# Plasma_speaker.net
KiCad netlist of a schematic drawn in EAGLE
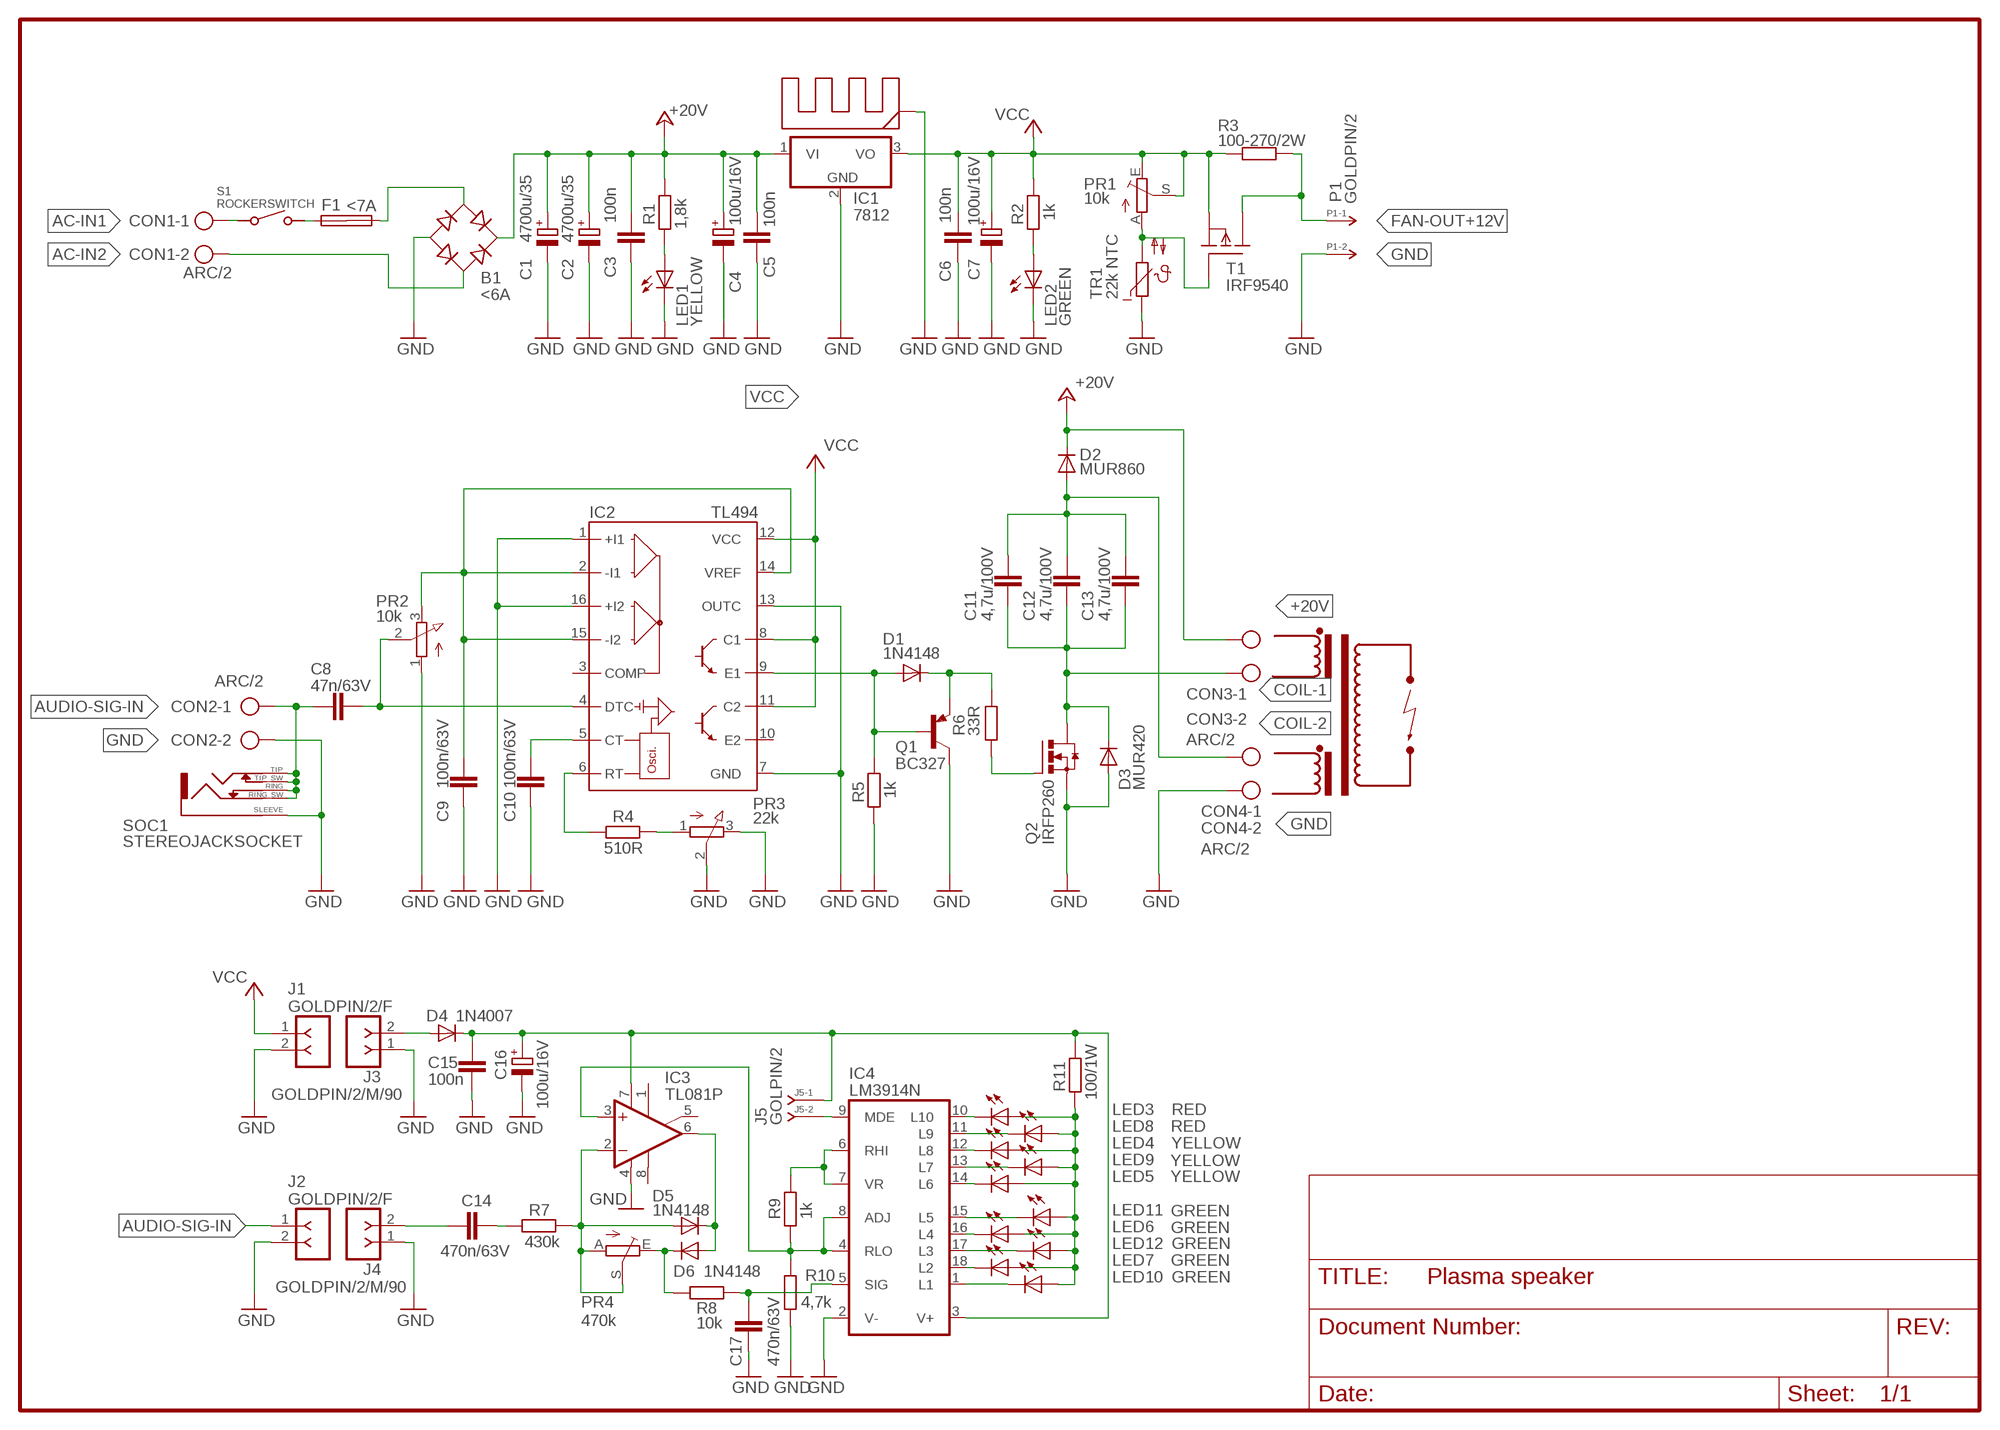
[diagram p0: schematic, sheet 1]

(export (version "E")
  (design (tool "Eeschema 10.0.6"))
  (components
    (comp (ref "B1")
      (value "<6A")
      (footprint "eagle-import:SKB32")
      (libsource (lib "eagle-import") (part "RECTIFIER-SKB32"))
    )
    (comp (ref "C1")
      (value "4700u/35")
      (footprint "eagle-import:E7,5-18")
      (libsource (lib "eagle-import") (part "CPOL-EUE7.5-18"))
    )
    (comp (ref "C2")
      (value "4700u/35")
      (footprint "eagle-import:E7,5-18")
      (libsource (lib "eagle-import") (part "CPOL-EUE7.5-18"))
    )
    (comp (ref "C3")
      (value "100n")
      (footprint "eagle-import:C025-025X050")
      (libsource (lib "eagle-import") (part "C-EU025-025X050"))
    )
    (comp (ref "C4")
      (value "100u/16V")
      (footprint "eagle-import:E2,5-5")
      (libsource (lib "eagle-import") (part "CPOL-EUE2.5-5"))
    )
    (comp (ref "C5")
      (value "100n")
      (footprint "eagle-import:C025-025X050")
      (libsource (lib "eagle-import") (part "C-EU025-025X050"))
    )
    (comp (ref "C6")
      (value "100n")
      (footprint "eagle-import:C025-025X050")
      (libsource (lib "eagle-import") (part "C-EU025-025X050"))
    )
    (comp (ref "C7")
      (value "100u/16V")
      (footprint "eagle-import:E2,5-5")
      (libsource (lib "eagle-import") (part "CPOL-EUE2.5-5"))
    )
    (comp (ref "C8")
      (value "47n/63V")
      (footprint "eagle-import:C050-025X075")
      (libsource (lib "eagle-import") (part "C-EU050-025X075"))
    )
    (comp (ref "C9")
      (value "100n/63V")
      (footprint "eagle-import:C050-025X075")
      (libsource (lib "eagle-import") (part "C-EU050-025X075"))
    )
    (comp (ref "C10")
      (value "100n/63V")
      (footprint "eagle-import:C050-025X075")
      (libsource (lib "eagle-import") (part "C-EU050-025X075"))
    )
    (comp (ref "C11")
      (value "4,7u/100V")
      (footprint "eagle-import:C275-093X316")
      (libsource (lib "eagle-import") (part "C-EU275-093X316"))
    )
    (comp (ref "C12")
      (value "4,7u/100V")
      (footprint "eagle-import:C275-093X316")
      (libsource (lib "eagle-import") (part "C-EU275-093X316"))
    )
    (comp (ref "C13")
      (value "4,7u/100V")
      (footprint "eagle-import:C275-093X316")
      (libsource (lib "eagle-import") (part "C-EU275-093X316"))
    )
    (comp (ref "C14")
      (value "470n/63V")
      (footprint "eagle-import:C050-050X075")
      (libsource (lib "eagle-import") (part "C-EU050-050X075"))
    )
    (comp (ref "C15")
      (value "100n")
      (footprint "eagle-import:C025-025X050")
      (libsource (lib "eagle-import") (part "C-EU025-025X050"))
    )
    (comp (ref "C16")
      (value "100u/16V")
      (footprint "eagle-import:E2,5-5")
      (libsource (lib "eagle-import") (part "CPOL-EUE2.5-5"))
    )
    (comp (ref "C17")
      (value "470n/63V")
      (footprint "eagle-import:C050-050X075")
      (libsource (lib "eagle-import") (part "C-EU050-050X075"))
    )
    (comp (ref "CON1")
      (value "ARC/2")
      (footprint "eagle-import:AK300_2")
      (libsource (lib "eagle-import") (part "AK300/2"))
    )
    (comp (ref "CON2")
      (value "ARC/2")
      (footprint "eagle-import:AK300_2")
      (libsource (lib "eagle-import") (part "AK300/2"))
    )
    (comp (ref "CON3")
      (value "ARC/2")
      (footprint "eagle-import:AK300_2")
      (libsource (lib "eagle-import") (part "AK300/2"))
    )
    (comp (ref "CON4")
      (value "ARC/2")
      (footprint "eagle-import:AK300_2")
      (libsource (lib "eagle-import") (part "AK300/2"))
    )
    (comp (ref "D1")
      (value "1N4148")
      (footprint "eagle-import:DO35-7")
      (libsource (lib "eagle-import") (part "1N4148DO35-7"))
    )
    (comp (ref "D2")
      (value "MUR860")
      (footprint "eagle-import:TO220ACS")
      (libsource (lib "eagle-import") (part "BYT08P"))
    )
    (comp (ref "D3")
      (value "MUR420")
      (footprint "eagle-import:SGA-10")
      (libsource (lib "eagle-import") (part "BY203"))
    )
    (comp (ref "D4")
      (value "1N4007")
      (footprint "eagle-import:DO41-10")
      (libsource (lib "eagle-import") (part "1N4004"))
    )
    (comp (ref "D5")
      (value "1N4148")
      (footprint "eagle-import:DO35-7")
      (libsource (lib "eagle-import") (part "1N4148DO35-7"))
    )
    (comp (ref "D6")
      (value "1N4148")
      (footprint "eagle-import:DO35-7")
      (libsource (lib "eagle-import") (part "1N4148DO35-7"))
    )
    (comp (ref "F1")
      (value "<7A")
      (footprint "eagle-import:SHK20L")
      (libsource (lib "eagle-import") (part "SHK20L"))
    )
    (comp (ref "IC1")
      (value "7812")
      (footprint "eagle-import:TO220V")
      (libsource (lib "eagle-import") (part "78TV12"))
    )
    (comp (ref "IC2")
      (value "TL494")
      (footprint "eagle-import:DIL16")
      (libsource (lib "eagle-import") (part "TL494NC"))
    )
    (comp (ref "IC3")
      (value "TL081P")
      (footprint "eagle-import:DIL08")
      (libsource (lib "eagle-import") (part "TL081P"))
    )
    (comp (ref "IC4")
      (value "LM3914N")
      (footprint "eagle-import:DIL18")
      (libsource (lib "eagle-import") (part "LM3914N"))
    )
    (comp (ref "J1")
      (value "GOLDPIN/2/F")
      (footprint "eagle-import:SIP-100-02-40Y")
      (libsource (lib "eagle-import") (part "F-1X02-SIP-100-40Y"))
    )
    (comp (ref "J2")
      (value "GOLDPIN/2/F")
      (footprint "eagle-import:SIP-100-02-40Y")
      (libsource (lib "eagle-import") (part "F-1X02-SIP-100-40Y"))
    )
    (comp (ref "J3")
      (value "GOLDPIN/2/M/90")
      (footprint "eagle-import:KK-4455-A02")
      (libsource (lib "eagle-import") (part "F-1X02-KK-4455-A02"))
    )
    (comp (ref "J4")
      (value "GOLDPIN/2/M/90")
      (footprint "eagle-import:KK-4455-A02")
      (libsource (lib "eagle-import") (part "F-1X02-KK-4455-A02"))
    )
    (comp (ref "J5")
      (value "GOLPIN/2")
      (footprint "eagle-import:SIP-100-02-40Y")
      (libsource (lib "eagle-import") (part "J-02-SIP-100-40Y"))
    )
    (comp (ref "LED1")
      (value "YELLOW")
      (footprint "eagle-import:LED5MM")
      (libsource (lib "eagle-import") (part "LED5MM"))
    )
    (comp (ref "LED2")
      (value "GREEN")
      (footprint "eagle-import:LED5MM")
      (libsource (lib "eagle-import") (part "LED5MM"))
    )
    (comp (ref "LED3")
      (value "RED")
      (footprint "eagle-import:LED5MM")
      (libsource (lib "eagle-import") (part "LED5MM"))
    )
    (comp (ref "LED4")
      (value "YELLOW")
      (footprint "eagle-import:LED5MM")
      (libsource (lib "eagle-import") (part "LED5MM"))
    )
    (comp (ref "LED5")
      (value "YELLOW")
      (footprint "eagle-import:LED5MM")
      (libsource (lib "eagle-import") (part "LED5MM"))
    )
    (comp (ref "LED6")
      (value "GREEN")
      (footprint "eagle-import:LED5MM")
      (libsource (lib "eagle-import") (part "LED5MM"))
    )
    (comp (ref "LED7")
      (value "GREEN")
      (footprint "eagle-import:LED5MM")
      (libsource (lib "eagle-import") (part "LED5MM"))
    )
    (comp (ref "LED8")
      (value "RED")
      (footprint "eagle-import:LED5MM")
      (libsource (lib "eagle-import") (part "LED5MM"))
    )
    (comp (ref "LED9")
      (value "YELLOW")
      (footprint "eagle-import:LED5MM")
      (libsource (lib "eagle-import") (part "LED5MM"))
    )
    (comp (ref "LED10")
      (value "GREEN")
      (footprint "eagle-import:LED5MM")
      (libsource (lib "eagle-import") (part "LED5MM"))
    )
    (comp (ref "LED11")
      (value "GREEN")
      (footprint "eagle-import:LED5MM")
      (libsource (lib "eagle-import") (part "LED5MM"))
    )
    (comp (ref "LED12")
      (value "GREEN")
      (footprint "eagle-import:LED5MM")
      (libsource (lib "eagle-import") (part "LED5MM"))
    )
    (comp (ref "P1")
      (value "GOLDPIN/2")
      (footprint "eagle-import:SIP-100-02-40Y")
      (libsource (lib "eagle-import") (part "P-02-SIP-100-40Y"))
    )
    (comp (ref "PR1")
      (value "10k")
      (footprint "eagle-import:CA6V")
      (libsource (lib "eagle-import") (part "TRIM_EU-CA6V"))
    )
    (comp (ref "PR2")
      (value "10k")
      (footprint "eagle-import:3RP_1610N")
      (libsource (lib "eagle-import") (part "3RP/1610N"))
    )
    (comp (ref "PR3")
      (value "22k")
      (footprint "eagle-import:3RP_1610N")
      (libsource (lib "eagle-import") (part "3RP/1610N"))
    )
    (comp (ref "PR4")
      (value "470k")
      (footprint "eagle-import:CA6V")
      (libsource (lib "eagle-import") (part "TRIM_EU-CA6V"))
    )
    (comp (ref "Q1")
      (value "BC327")
      (footprint "eagle-import:TO92-EBC")
      (libsource (lib "eagle-import") (part "-PNP-TO92-EBCBC327-25"))
    )
    (comp (ref "Q2")
      (value "IRFP260")
      (footprint "eagle-import:TO247BV")
      (libsource (lib "eagle-import") (part "IRFP240"))
    )
    (comp (ref "R1")
      (value "1,8k")
      (footprint "eagle-import:0204_7")
      (libsource (lib "eagle-import") (part "R-EU_0204/7"))
    )
    (comp (ref "R2")
      (value "1k")
      (footprint "eagle-import:0204_7")
      (libsource (lib "eagle-import") (part "R-EU_0204/7"))
    )
    (comp (ref "R3")
      (value "100-270/2W")
      (footprint "eagle-import:0309_12")
      (libsource (lib "eagle-import") (part "R-EU_0309/12"))
    )
    (comp (ref "R4")
      (value "510R")
      (footprint "eagle-import:0204_7")
      (libsource (lib "eagle-import") (part "R-EU_0204/7"))
    )
    (comp (ref "R5")
      (value "1k")
      (footprint "eagle-import:0204_7")
      (libsource (lib "eagle-import") (part "R-EU_0204/7"))
    )
    (comp (ref "R6")
      (value "33R")
      (footprint "eagle-import:0207_10")
      (libsource (lib "eagle-import") (part "R-EU_0207/10"))
    )
    (comp (ref "R7")
      (value "430k")
      (footprint "eagle-import:0204_7")
      (libsource (lib "eagle-import") (part "R-EU_0204/7"))
    )
    (comp (ref "R8")
      (value "10k")
      (footprint "eagle-import:0204_7")
      (libsource (lib "eagle-import") (part "R-EU_0204/7"))
    )
    (comp (ref "R9")
      (value "1k")
      (footprint "eagle-import:0204_7")
      (libsource (lib "eagle-import") (part "R-EU_0204/7"))
    )
    (comp (ref "R10")
      (value "4,7k")
      (footprint "eagle-import:0204_7")
      (libsource (lib "eagle-import") (part "R-EU_0204/7"))
    )
    (comp (ref "R11")
      (value "100/1W")
      (footprint "eagle-import:0411_15")
      (libsource (lib "eagle-import") (part "R-EU_0411/15"))
    )
    (comp (ref "RAD1")
      (value "TO3")
      (footprint "eagle-import:RADIATOR")
      (libsource (lib "eagle-import") (part "RADIATOR-A"))
    )
    (comp (ref "S1")
      (value "ROCKERSWITCH")
      (footprint "eagle-import:ROCKER")
      (libsource (lib "eagle-import") (part "ROCKERSWITCH"))
    )
    (comp (ref "SOC1")
      (value "STEREOJACKSOCKET")
      (footprint "eagle-import:PICAXE_STEREOJACKSOCKET")
      (libsource (lib "eagle-import") (part "PICAXE_STEREOJACKSOCKET"))
    )
    (comp (ref "T1")
      (value "IRF9540")
      (footprint "eagle-import:TO220")
      (libsource (lib "eagle-import") (part "IRF9530"))
    )
    (comp (ref "TR1")
      (value "22k NTC")
      (footprint "eagle-import:P640")
      (libsource (lib "eagle-import") (part "NTC640"))
    )
  )
  (nets
    (net (code "1") (name "+20V") (class "Default")
      (node (ref "B1") (pin "+") (pinfunction "+_+") (pintype "passive"))
      (node (ref "C1") (pin "+") (pinfunction "+_+") (pintype "passive"))
      (node (ref "C2") (pin "+") (pinfunction "+_+") (pintype "passive"))
      (node (ref "C3") (pin "1") (pinfunction "1_1") (pintype "passive"))
      (node (ref "C4") (pin "+") (pinfunction "+_+") (pintype "passive"))
      (node (ref "C5") (pin "1") (pinfunction "1_1") (pintype "passive"))
      (node (ref "CON3") (pin "1") (pinfunction "KL_1") (pintype "passive"))
      (node (ref "D2") (pin "C") (pinfunction "C_C") (pintype "passive"))
      (node (ref "IC1") (pin "1") (pinfunction "VI_1") (pintype "input"))
      (node (ref "R1") (pin "1") (pinfunction "1_1") (pintype "passive"))
    )
    (net (code "2") (name "AC-IN1") (class "Default")
      (node (ref "CON1") (pin "1") (pinfunction "KL_1") (pintype "passive"))
      (node (ref "S1") (pin "IN1") (pinfunction "IN_IN1") (pintype "input"))
      (node (ref "S1") (pin "IN2") (pinfunction "IN_IN2") (pintype "input"))
    )
    (net (code "3") (name "AC-IN2") (class "Default")
      (node (ref "B1") (pin "AC2") (pinfunction "AC2_AC2") (pintype "passive"))
      (node (ref "CON1") (pin "2") (pinfunction "KL_2") (pintype "passive"))
    )
    (net (code "4") (name "AUDIO-SIG-IN") (class "Default")
      (node (ref "C8") (pin "2") (pinfunction "2_2") (pintype "passive"))
      (node (ref "CON2") (pin "1") (pinfunction "KL_1") (pintype "passive"))
      (node (ref "J2") (pin "1") (pinfunction "1_1") (pintype "passive"))
      (node (ref "SOC1") (pin "RING") (pinfunction "RING_RING") (pintype "bidirectional"))
      (node (ref "SOC1") (pin "RING_SW") (pinfunction "RING-SW_RING_SW") (pintype "bidirectional"))
      (node (ref "SOC1") (pin "TIP") (pinfunction "TIP_TIP") (pintype "bidirectional"))
      (node (ref "SOC1") (pin "TIP_SW") (pinfunction "TIP-SW_TIP_SW") (pintype "bidirectional"))
    )
    (net (code "5") (name "COIL-1") (class "Default")
      (node (ref "C11") (pin "2") (pinfunction "2_2") (pintype "passive"))
      (node (ref "C12") (pin "2") (pinfunction "2_2") (pintype "passive"))
      (node (ref "C13") (pin "2") (pinfunction "2_2") (pintype "passive"))
      (node (ref "CON3") (pin "2") (pinfunction "KL_2") (pintype "passive"))
      (node (ref "D3") (pin "C") (pinfunction "C_C") (pintype "passive"))
      (node (ref "Q2") (pin "D") (pinfunction "D_D") (pintype "passive"))
    )
    (net (code "6") (name "COIL-2") (class "Default")
      (node (ref "C11") (pin "1") (pinfunction "1_1") (pintype "passive"))
      (node (ref "C12") (pin "1") (pinfunction "1_1") (pintype "passive"))
      (node (ref "C13") (pin "1") (pinfunction "1_1") (pintype "passive"))
      (node (ref "CON4") (pin "1") (pinfunction "KL_1") (pintype "passive"))
      (node (ref "D2") (pin "A") (pinfunction "A_A") (pintype "passive"))
    )
    (net (code "7") (name "FAN-OUT+12V") (class "Default")
      (node (ref "P1") (pin "1") (pinfunction "P_1") (pintype "passive"))
      (node (ref "R3") (pin "2") (pinfunction "2_2") (pintype "passive"))
      (node (ref "T1") (pin "2") (pinfunction "D_2") (pintype "passive"))
    )
    (net (code "8") (name "GND") (class "Default")
      (node (ref "B1") (pin "-") (pinfunction "-_-") (pintype "passive"))
      (node (ref "C1") (pin "-") (pinfunction "-_-") (pintype "passive"))
      (node (ref "C10") (pin "2") (pinfunction "2_2") (pintype "passive"))
      (node (ref "C15") (pin "2") (pinfunction "2_2") (pintype "passive"))
      (node (ref "C16") (pin "-") (pinfunction "-_-") (pintype "passive"))
      (node (ref "C17") (pin "1") (pinfunction "1_1") (pintype "passive"))
      (node (ref "C2") (pin "-") (pinfunction "-_-") (pintype "passive"))
      (node (ref "C3") (pin "2") (pinfunction "2_2") (pintype "passive"))
      (node (ref "C4") (pin "-") (pinfunction "-_-") (pintype "passive"))
      (node (ref "C5") (pin "2") (pinfunction "2_2") (pintype "passive"))
      (node (ref "C6") (pin "2") (pinfunction "2_2") (pintype "passive"))
      (node (ref "C7") (pin "-") (pinfunction "-_-") (pintype "passive"))
      (node (ref "C9") (pin "2") (pinfunction "2_2") (pintype "passive"))
      (node (ref "CON2") (pin "2") (pinfunction "KL_2") (pintype "passive"))
      (node (ref "CON4") (pin "2") (pinfunction "KL_2") (pintype "passive"))
      (node (ref "D3") (pin "A") (pinfunction "A_A") (pintype "passive"))
      (node (ref "IC1") (pin "2") (pinfunction "GND_2") (pintype "passive"))
      (node (ref "IC2") (pin "1") (pinfunction "+I1_1") (pintype "input"))
      (node (ref "IC2") (pin "13") (pinfunction "OUTC_13") (pintype "output"))
      (node (ref "IC2") (pin "16") (pinfunction "+I2_16") (pintype "input"))
      (node (ref "IC2") (pin "7") (pinfunction "GND_7") (pintype "power_in"))
      (node (ref "IC3") (pin "4") (pinfunction "V-_4") (pintype "power_in"))
      (node (ref "IC4") (pin "2") (pinfunction "V-_2") (pintype "power_in"))
      (node (ref "J1") (pin "2") (pinfunction "2_2") (pintype "passive"))
      (node (ref "J2") (pin "2") (pinfunction "2_2") (pintype "passive"))
      (node (ref "J3") (pin "1") (pinfunction "1_1") (pintype "passive"))
      (node (ref "J4") (pin "1") (pinfunction "1_1") (pintype "passive"))
      (node (ref "LED1") (pin "K") (pinfunction "C_K") (pintype "passive"))
      (node (ref "LED2") (pin "K") (pinfunction "C_K") (pintype "passive"))
      (node (ref "P1") (pin "2") (pinfunction "P_2") (pintype "passive"))
      (node (ref "PR2") (pin "1") (pinfunction "A_1") (pintype "passive"))
      (node (ref "PR3") (pin "2") (pinfunction "S_2") (pintype "passive"))
      (node (ref "PR3") (pin "3") (pinfunction "E_3") (pintype "passive"))
      (node (ref "Q1") (pin "C") (pinfunction "C_C") (pintype "passive"))
      (node (ref "Q2") (pin "S") (pinfunction "S_S") (pintype "passive"))
      (node (ref "R10") (pin "2") (pinfunction "2_2") (pintype "passive"))
      (node (ref "R5") (pin "1") (pinfunction "1_1") (pintype "passive"))
      (node (ref "RAD1") (pin "GND") (pinfunction "P$1_GND") (pintype "bidirectional"))
      (node (ref "SOC1") (pin "SLEEVE") (pinfunction "SLEEVE_SLEEVE") (pintype "bidirectional"))
      (node (ref "TR1") (pin "1") (pinfunction "1_1") (pintype "passive"))
    )
    (net (code "9") (name "Net-(B1-PadAC1)") (class "Default")
      (node (ref "B1") (pin "AC1") (pinfunction "AC1_AC1") (pintype "passive"))
      (node (ref "F1") (pin "2A") (pinfunction "2A_2A") (pintype "passive"))
    )
    (net (code "10") (name "Net-(C14-Pad1)") (class "Default")
      (node (ref "C14") (pin "1") (pinfunction "1_1") (pintype "passive"))
      (node (ref "J4") (pin "2") (pinfunction "2_2") (pintype "passive"))
    )
    (net (code "11") (name "Net-(C14-Pad2)") (class "Default")
      (node (ref "C14") (pin "2") (pinfunction "2_2") (pintype "passive"))
      (node (ref "R7") (pin "2") (pinfunction "2_2") (pintype "passive"))
    )
    (net (code "12") (name "Net-(D1-PadC)") (class "Default")
      (node (ref "D1") (pin "C") (pinfunction "C_C") (pintype "passive"))
      (node (ref "Q1") (pin "E") (pinfunction "E_E") (pintype "passive"))
      (node (ref "R6") (pin "2") (pinfunction "2_2") (pintype "passive"))
    )
    (net (code "13") (name "Net-(D4-PadA)") (class "Default")
      (node (ref "D4") (pin "A") (pinfunction "A_A") (pintype "passive"))
      (node (ref "J3") (pin "2") (pinfunction "2_2") (pintype "passive"))
    )
    (net (code "14") (name "Net-(D6-PadC)") (class "Default")
      (node (ref "D6") (pin "C") (pinfunction "C_C") (pintype "passive"))
      (node (ref "PR4") (pin "E") (pinfunction "E_E") (pintype "passive"))
      (node (ref "R8") (pin "2") (pinfunction "2_2") (pintype "passive"))
    )
    (net (code "15") (name "Net-(F1-Pad1A)") (class "Default")
      (node (ref "F1") (pin "1A") (pinfunction "1A_1A") (pintype "passive"))
      (node (ref "S1") (pin "OUT") (pinfunction "OUT_OUT") (pintype "output"))
    )
    (net (code "16") (name "Net-(IC2--I1)") (class "Default")
      (node (ref "C9") (pin "1") (pinfunction "1_1") (pintype "passive"))
      (node (ref "IC2") (pin "14") (pinfunction "VREF_14") (pintype "input"))
      (node (ref "IC2") (pin "15") (pinfunction "-I2_15") (pintype "input"))
      (node (ref "IC2") (pin "2") (pinfunction "-I1_2") (pintype "input"))
      (node (ref "PR2") (pin "3") (pinfunction "E_3") (pintype "passive"))
    )
    (net (code "17") (name "Net-(IC2-CT)") (class "Default")
      (node (ref "C10") (pin "1") (pinfunction "1_1") (pintype "passive"))
      (node (ref "IC2") (pin "5") (pinfunction "CT_5") (pintype "input"))
    )
    (net (code "18") (name "Net-(IC2-DTC)") (class "Default")
      (node (ref "C8") (pin "1") (pinfunction "1_1") (pintype "passive"))
      (node (ref "IC2") (pin "4") (pinfunction "DTC_4") (pintype "input"))
      (node (ref "PR2") (pin "2") (pinfunction "S_2") (pintype "passive"))
    )
    (net (code "19") (name "Net-(IC2-E1)") (class "Default")
      (node (ref "D1") (pin "A") (pinfunction "A_A") (pintype "passive"))
      (node (ref "IC2") (pin "9") (pinfunction "E1_9") (pintype "passive"))
      (node (ref "Q1") (pin "B") (pinfunction "B_B") (pintype "passive"))
      (node (ref "R5") (pin "2") (pinfunction "2_2") (pintype "passive"))
    )
    (net (code "20") (name "Net-(IC2-RT)") (class "Default")
      (node (ref "IC2") (pin "6") (pinfunction "RT_6") (pintype "input"))
      (node (ref "R4") (pin "2") (pinfunction "2_2") (pintype "passive"))
    )
    (net (code "21") (name "Net-(IC3-+IN)") (class "Default")
      (node (ref "IC3") (pin "3") (pinfunction "+IN_3") (pintype "input"))
      (node (ref "IC4") (pin "4") (pinfunction "RLO_4") (pintype "input"))
      (node (ref "IC4") (pin "8") (pinfunction "ADJ_8") (pintype "input"))
      (node (ref "R10") (pin "1") (pinfunction "1_1") (pintype "passive"))
      (node (ref "R9") (pin "2") (pinfunction "2_2") (pintype "passive"))
    )
    (net (code "22") (name "Net-(IC3--IN)") (class "Default")
      (node (ref "D5") (pin "A") (pinfunction "A_A") (pintype "passive"))
      (node (ref "IC3") (pin "2") (pinfunction "-IN_2") (pintype "input"))
      (node (ref "PR4") (pin "A") (pinfunction "A_A") (pintype "passive"))
      (node (ref "PR4") (pin "S") (pinfunction "S_S") (pintype "passive"))
      (node (ref "R7") (pin "1") (pinfunction "1_1") (pintype "passive"))
    )
    (net (code "23") (name "Net-(IC3-OUT)") (class "Default")
      (node (ref "D5") (pin "C") (pinfunction "C_C") (pintype "passive"))
      (node (ref "D6") (pin "A") (pinfunction "A_A") (pintype "passive"))
      (node (ref "IC3") (pin "6") (pinfunction "OUT_6") (pintype "output"))
    )
    (net (code "24") (name "Net-(IC3-V+)") (class "Default")
      (node (ref "C15") (pin "1") (pinfunction "1_1") (pintype "passive"))
      (node (ref "C16") (pin "+") (pinfunction "+_+") (pintype "passive"))
      (node (ref "D4") (pin "C") (pinfunction "C_C") (pintype "passive"))
      (node (ref "IC3") (pin "7") (pinfunction "V+_7") (pintype "power_in"))
      (node (ref "IC4") (pin "3") (pinfunction "V+_3") (pintype "power_in"))
      (node (ref "J5") (pin "1") (pinfunction "J_1") (pintype "passive"))
      (node (ref "R11") (pin "2") (pinfunction "2_2") (pintype "passive"))
    )
    (net (code "25") (name "Net-(IC4-L1)") (class "Default")
      (node (ref "IC4") (pin "1") (pinfunction "L1_1") (pintype "output"))
      (node (ref "LED10") (pin "K") (pinfunction "C_K") (pintype "passive"))
    )
    (net (code "26") (name "Net-(IC4-L2)") (class "Default")
      (node (ref "IC4") (pin "18") (pinfunction "L2_18") (pintype "output"))
      (node (ref "LED7") (pin "K") (pinfunction "C_K") (pintype "passive"))
    )
    (net (code "27") (name "Net-(IC4-L3)") (class "Default")
      (node (ref "IC4") (pin "17") (pinfunction "L3_17") (pintype "output"))
      (node (ref "LED12") (pin "K") (pinfunction "C_K") (pintype "passive"))
    )
    (net (code "28") (name "Net-(IC4-L4)") (class "Default")
      (node (ref "IC4") (pin "16") (pinfunction "L4_16") (pintype "output"))
      (node (ref "LED6") (pin "K") (pinfunction "C_K") (pintype "passive"))
    )
    (net (code "29") (name "Net-(IC4-L5)") (class "Default")
      (node (ref "IC4") (pin "15") (pinfunction "L5_15") (pintype "output"))
      (node (ref "LED11") (pin "K") (pinfunction "C_K") (pintype "passive"))
    )
    (net (code "30") (name "Net-(IC4-L6)") (class "Default")
      (node (ref "IC4") (pin "14") (pinfunction "L6_14") (pintype "output"))
      (node (ref "LED5") (pin "K") (pinfunction "C_K") (pintype "passive"))
    )
    (net (code "31") (name "Net-(IC4-L7)") (class "Default")
      (node (ref "IC4") (pin "13") (pinfunction "L7_13") (pintype "output"))
      (node (ref "LED9") (pin "K") (pinfunction "C_K") (pintype "passive"))
    )
    (net (code "32") (name "Net-(IC4-L8)") (class "Default")
      (node (ref "IC4") (pin "12") (pinfunction "L8_12") (pintype "output"))
      (node (ref "LED4") (pin "K") (pinfunction "C_K") (pintype "passive"))
    )
    (net (code "33") (name "Net-(IC4-L9)") (class "Default")
      (node (ref "IC4") (pin "11") (pinfunction "L9_11") (pintype "output"))
      (node (ref "LED8") (pin "K") (pinfunction "C_K") (pintype "passive"))
    )
    (net (code "34") (name "Net-(IC4-L10)") (class "Default")
      (node (ref "IC4") (pin "10") (pinfunction "L10_10") (pintype "output"))
      (node (ref "LED3") (pin "K") (pinfunction "C_K") (pintype "passive"))
    )
    (net (code "35") (name "Net-(IC4-MDE)") (class "Default")
      (node (ref "IC4") (pin "9") (pinfunction "MDE_9") (pintype "input"))
      (node (ref "J5") (pin "2") (pinfunction "J_2") (pintype "passive"))
    )
    (net (code "36") (name "Net-(IC4-RHI)") (class "Default")
      (node (ref "IC4") (pin "6") (pinfunction "RHI_6") (pintype "input"))
      (node (ref "IC4") (pin "7") (pinfunction "VR_7") (pintype "output"))
      (node (ref "R9") (pin "1") (pinfunction "1_1") (pintype "passive"))
    )
    (net (code "37") (name "Net-(IC4-SIG)") (class "Default")
      (node (ref "C17") (pin "2") (pinfunction "2_2") (pintype "passive"))
      (node (ref "IC4") (pin "5") (pinfunction "SIG_5") (pintype "input"))
      (node (ref "R8") (pin "1") (pinfunction "1_1") (pintype "passive"))
    )
    (net (code "38") (name "Net-(LED1-PadA)") (class "Default")
      (node (ref "LED1") (pin "A") (pinfunction "A_A") (pintype "passive"))
      (node (ref "R1") (pin "2") (pinfunction "2_2") (pintype "passive"))
    )
    (net (code "39") (name "Net-(LED2-PadA)") (class "Default")
      (node (ref "LED2") (pin "A") (pinfunction "A_A") (pintype "passive"))
      (node (ref "R2") (pin "2") (pinfunction "2_2") (pintype "passive"))
    )
    (net (code "40") (name "Net-(LED10-PadA)") (class "Default")
      (node (ref "LED10") (pin "A") (pinfunction "A_A") (pintype "passive"))
      (node (ref "LED11") (pin "A") (pinfunction "A_A") (pintype "passive"))
      (node (ref "LED12") (pin "A") (pinfunction "A_A") (pintype "passive"))
      (node (ref "LED3") (pin "A") (pinfunction "A_A") (pintype "passive"))
      (node (ref "LED4") (pin "A") (pinfunction "A_A") (pintype "passive"))
      (node (ref "LED5") (pin "A") (pinfunction "A_A") (pintype "passive"))
      (node (ref "LED6") (pin "A") (pinfunction "A_A") (pintype "passive"))
      (node (ref "LED7") (pin "A") (pinfunction "A_A") (pintype "passive"))
      (node (ref "LED8") (pin "A") (pinfunction "A_A") (pintype "passive"))
      (node (ref "LED9") (pin "A") (pinfunction "A_A") (pintype "passive"))
      (node (ref "R11") (pin "1") (pinfunction "1_1") (pintype "passive"))
    )
    (net (code "41") (name "Net-(PR3-A)") (class "Default")
      (node (ref "PR3") (pin "1") (pinfunction "A_1") (pintype "passive"))
      (node (ref "R4") (pin "1") (pinfunction "1_1") (pintype "passive"))
    )
    (net (code "42") (name "Net-(Q2-PadG)") (class "Default")
      (node (ref "Q2") (pin "G") (pinfunction "G_G") (pintype "passive"))
      (node (ref "R6") (pin "1") (pinfunction "1_1") (pintype "passive"))
    )
    (net (code "43") (name "Net-(T1-G)") (class "Default")
      (node (ref "PR1") (pin "A") (pinfunction "A_A") (pintype "passive"))
      (node (ref "T1") (pin "1") (pinfunction "G_1") (pintype "passive"))
      (node (ref "TR1") (pin "2") (pinfunction "2_2") (pintype "passive"))
    )
    (net (code "44") (name "VCC") (class "Default")
      (node (ref "C6") (pin "1") (pinfunction "1_1") (pintype "passive"))
      (node (ref "C7") (pin "+") (pinfunction "+_+") (pintype "passive"))
      (node (ref "IC1") (pin "3") (pinfunction "VO_3") (pintype "passive"))
      (node (ref "IC2") (pin "11") (pinfunction "C2_11") (pintype "passive"))
      (node (ref "IC2") (pin "12") (pinfunction "VCC_12") (pintype "power_in"))
      (node (ref "IC2") (pin "8") (pinfunction "C1_8") (pintype "passive"))
      (node (ref "J1") (pin "1") (pinfunction "1_1") (pintype "passive"))
      (node (ref "PR1") (pin "E") (pinfunction "E_E") (pintype "passive"))
      (node (ref "PR1") (pin "S") (pinfunction "S_S") (pintype "passive"))
      (node (ref "R2") (pin "1") (pinfunction "1_1") (pintype "passive"))
      (node (ref "R3") (pin "1") (pinfunction "1_1") (pintype "passive"))
      (node (ref "T1") (pin "3") (pinfunction "S_3") (pintype "passive"))
    )
    (net (code "45") (name "unconnected-(F1-Pad1B)") (class "Default")
      (node (ref "F1") (pin "1B") (pinfunction "1B_1B") (pintype "passive"))
    )
    (net (code "46") (name "unconnected-(F1-Pad2B)") (class "Default")
      (node (ref "F1") (pin "2B") (pinfunction "2B_2B") (pintype "passive"))
    )
    (net (code "47") (name "unconnected-(IC2-COMP-Pad3)") (class "Default")
      (node (ref "IC2") (pin "3") (pinfunction "COMP_3") (pintype "passive"))
    )
    (net (code "48") (name "unconnected-(IC2-E2-Pad10)") (class "Default")
      (node (ref "IC2") (pin "10") (pinfunction "E2_10") (pintype "passive"))
    )
    (net (code "49") (name "unconnected-(IC3-ON1-Pad1)") (class "Default")
      (node (ref "IC3") (pin "1") (pinfunction "ON1_1") (pintype "passive"))
    )
    (net (code "50") (name "unconnected-(IC3-ON2-Pad5)") (class "Default")
      (node (ref "IC3") (pin "5") (pinfunction "ON2_5") (pintype "passive"))
    )
    (net (code "51") (name "unconnected-(IC3-OPT-Pad8)") (class "Default")
      (node (ref "IC3") (pin "8") (pinfunction "OPT_8") (pintype "passive"))
    )
  )
)
